# tsmp77000_breakout.net
KiCad netlist of a schematic drawn in EAGLE
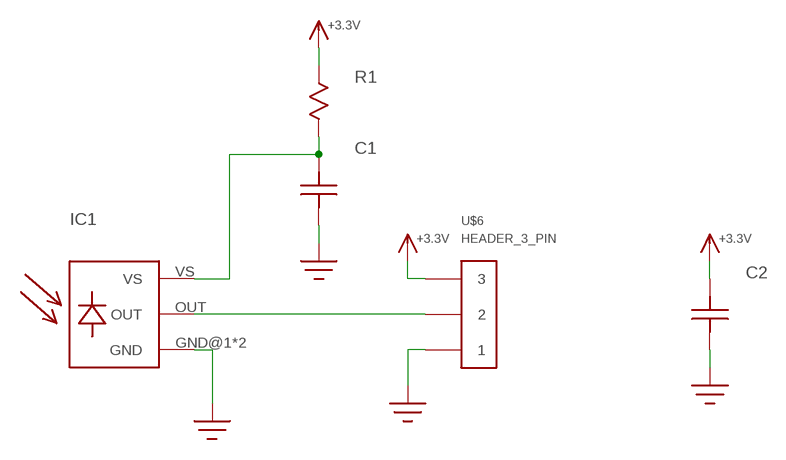
[diagram p0: schematic, sheet 1]

(export (version "E")
  (design (tool "Eeschema 10.0.6"))
  (components
    (comp (ref "C1")
      (value "C0805")
      (footprint "eagle-import:0805")
      (libsource (lib "eagle-import") (part "C0805"))
    )
    (comp (ref "C2")
      (value "C1206")
      (footprint "eagle-import:1206")
      (libsource (lib "eagle-import") (part "C1206"))
    )
    (comp (ref "IC1")
      (value "TSMP77000")
      (footprint "eagle-import:TSMP77000")
      (libsource (lib "eagle-import") (part "TSMP77000"))
    )
    (comp (ref "R1")
      (value "R0805")
      (footprint "eagle-import:R0805")
      (libsource (lib "eagle-import") (part "R0805"))
    )
    (comp (ref "U$6")
      (value "HEADER_3_PIN")
      (footprint "eagle-import:HEADER_3_PIN")
      (libsource (lib "eagle-import") (part "HEADER_3_PIN"))
    )
  )
  (nets
    (net (code "1") (name "+3.3V") (class "Default")
      (node (ref "C2") (pin "P$2") (pinfunction "P$2_P$2") (pintype "bidirectional"))
      (node (ref "R1") (pin "P$1") (pinfunction "P$3_P$1") (pintype "bidirectional"))
      (node (ref "U$6") (pin "3") (pinfunction "3_3") (pintype "bidirectional"))
    )
    (net (code "2") (name "GND") (class "Default")
      (node (ref "C1") (pin "P$1") (pinfunction "P$1_P$1") (pintype "bidirectional"))
      (node (ref "C2") (pin "P$1") (pinfunction "P$1_P$1") (pintype "bidirectional"))
      (node (ref "IC1") (pin "GND@1") (pinfunction "GND_GND@1") (pintype "bidirectional"))
      (node (ref "IC1") (pin "GND@2") (pinfunction "GND_GND@2") (pintype "bidirectional"))
      (node (ref "U$6") (pin "1") (pinfunction "1_1") (pintype "bidirectional"))
    )
    (net (code "3") (name "Net-(IC1-PadOUT)") (class "Default")
      (node (ref "IC1") (pin "OUT") (pinfunction "OUT_OUT") (pintype "bidirectional"))
      (node (ref "U$6") (pin "2") (pinfunction "2_2") (pintype "bidirectional"))
    )
    (net (code "4") (name "Net-(R1-P$4)") (class "Default")
      (node (ref "C1") (pin "P$2") (pinfunction "P$2_P$2") (pintype "bidirectional"))
      (node (ref "IC1") (pin "VS") (pinfunction "VS_VS") (pintype "bidirectional"))
      (node (ref "R1") (pin "P$2") (pinfunction "P$4_P$2") (pintype "bidirectional"))
    )
  )
)
